# 05_HMS_HMI.net
KiCad netlist of a schematic drawn in Altium Designer
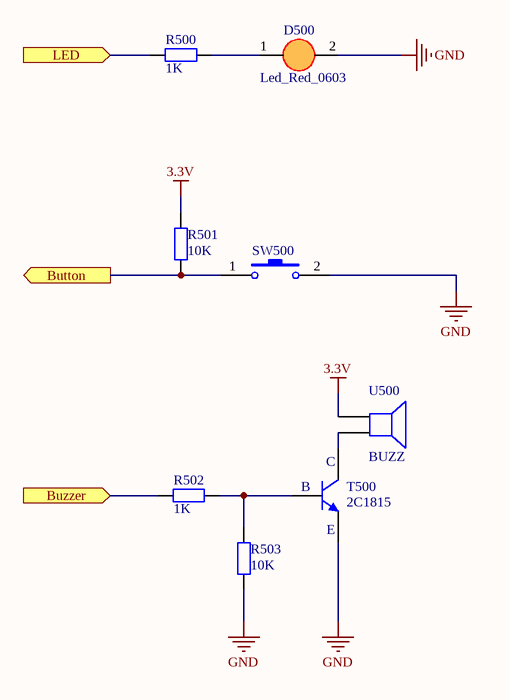
[diagram p0: [05].HMS.HMI.SchDoc]

(export (version "E")
  (design (tool "Eeschema 10.0.6"))
  (components
    (comp (ref "D500")
      (value "Led_Red_0603")
      (footprint "LED_0603_RED")
      (description "LED RED CLEAR CHIP SMD 0603")
      (fields (field (name "MPN") "NCD0603R1") (field (name "MFR") "LinhKienChatLuong"))
      (libsource (lib "04.Diode_Led") (part "LED_3MM"))
    )
    (comp (ref "R500")
      (value "1K")
      (footprint "RES_0402(1005)")
      (description "RES 1K OHM 1% 1/8W 0402")
      (fields (field (name "MPN") "RC0402FR-071KL") (field (name "MFR") "YAGEO"))
      (libsource (lib "02.Resistor.0402") (part "RC0402FR-071KL"))
    )
    (comp (ref "R501")
      (value "10K")
      (footprint "RES_0402(1005)")
      (description "RES 10K OHM 5% 1/8W 0402")
      (fields (field (name "MPN") "RC0402JR-0710KL") (field (name "MFR") "YAGEO"))
      (libsource (lib "") (part "RC0402FR-071KL_1"))
    )
    (comp (ref "R502")
      (value "1K")
      (footprint "RES_0402(1005)")
      (description "RES 1K OHM 1% 1/16W 0402")
      (fields (field (name "MPN") "RC0402FR-131KL") (field (name "MFR") "YAGEO"))
      (libsource (lib "02.Resistor.0402") (part "RC0402FR-131KL"))
    )
    (comp (ref "R503")
      (value "10K")
      (footprint "RES_0402(1005)")
      (description "RES SMD 10K OHM 5% 1/16W 0402")
      (fields (field (name "MPN") "RC0402JR-074K7P") (field (name "MFR") "YAGEO"))
      (libsource (lib "02.Resistor.0402") (part "RC0402JR-074K7P"))
    )
    (comp (ref "SW500")
      (value "SW-4P-S")
      (footprint "SW 2P 90 Dgerees")
      (description "Switch Small 4 Pin DIP")
      (fields (field (name "MPN") "Button 4P 6x6x6mm nghiêng") (field (name "PUBLISHER") "Altium Limited"))
      (libsource (lib "10.Miscellaneous") (part "SW-2PIN-SMALL"))
    )
    (comp (ref "T500")
      (value "2C1815")
      (footprint "SOT23-3")
      (description "D882 2SD882 NPN Transistor 3A 30V SOT-89")
      (fields (field (name "MPN") "2SD882") (field (name "MFR") "JCET"))
      (libsource (lib "15.Transistor_Mosfet") (part "C18C5"))
    )
    (comp (ref "U500")
      (value "BUZZ")
      (footprint "BUZZER_THROUGH_5MM")
      (description "Buzz TMB09A03 3V 9x5.5mm")
      (fields
        (field (name "BAPARTNUMBER") "VT-0")
        (field (name "MPN") "TMB09A03")
        (field (name "PUBLISHER") "Altium Limited")
      )
      (libsource (lib "08.Miscellaneous") (part "Speaker"))
    )
  )
  (nets
    (net (code "1") (name "/Button") (class "Default")
      (node (ref "R501") (pin "1") (pinfunction "1_1") (pintype "passive"))
      (node (ref "SW500") (pin "1") (pinfunction "1_1") (pintype "passive"))
    )
    (net (code "2") (name "/Buzzer") (class "Default")
      (node (ref "R502") (pin "1") (pinfunction "1_1") (pintype "passive"))
    )
    (net (code "3") (name "/LED") (class "Default")
      (node (ref "R500") (pin "1") (pinfunction "1_1") (pintype "passive"))
    )
    (net (code "4") (name "3.3V") (class "Default")
      (node (ref "R501") (pin "2") (pinfunction "2_2") (pintype "passive"))
      (node (ref "U500") (pin "1") (pinfunction "1_1") (pintype "passive"))
    )
    (net (code "5") (name "GND") (class "Default")
      (node (ref "D500") (pin "2") (pinfunction "K_2") (pintype "passive"))
      (node (ref "R503") (pin "1") (pinfunction "1_1") (pintype "passive"))
      (node (ref "SW500") (pin "2") (pinfunction "2_2") (pintype "passive"))
      (node (ref "T500") (pin "2") (pinfunction "2_2") (pintype "passive"))
    )
    (net (code "6") (name "Net-(D500-A)") (class "Default")
      (node (ref "D500") (pin "1") (pinfunction "A_1") (pintype "passive"))
      (node (ref "R500") (pin "2") (pinfunction "2_2") (pintype "passive"))
    )
    (net (code "7") (name "Net-(R502-Pad2)") (class "Default")
      (node (ref "R502") (pin "2") (pinfunction "2_2") (pintype "passive"))
      (node (ref "R503") (pin "2") (pinfunction "2_2") (pintype "passive"))
      (node (ref "T500") (pin "1") (pinfunction "1_1") (pintype "passive"))
    )
    (net (code "8") (name "Net-(T500-Pad3)") (class "Default")
      (node (ref "T500") (pin "3") (pinfunction "3_3") (pintype "passive"))
      (node (ref "U500") (pin "2") (pinfunction "2_2") (pintype "passive"))
    )
  )
)
